# 9_RGB_TOUCH.net
KiCad netlist of a schematic drawn in Altium Designer
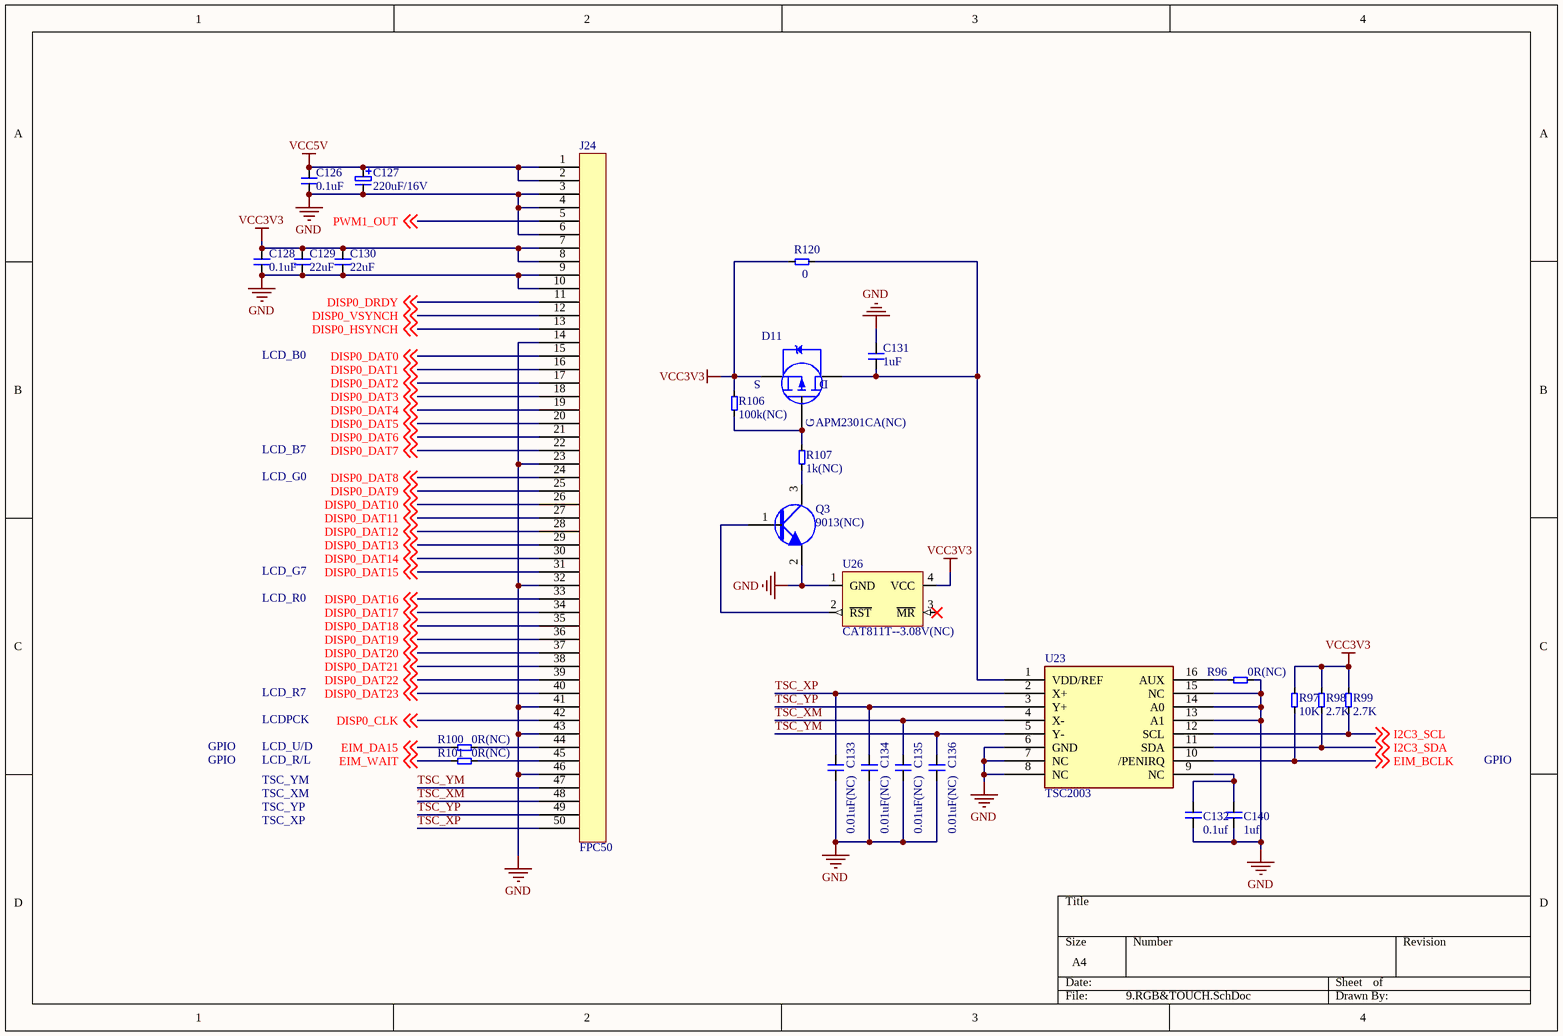
[diagram p0: 9.RGB&TOUCH.SchDoc]

(export (version "E")
  (design (tool "Eeschema 10.0.6"))
  (components
    (comp (ref "C126")
      (value "0.1uF")
      (footprint "0603C")
      (description "电容")
      (libsource (lib "LDT-SCH") (part "电容"))
    )
    (comp (ref "C127")
      (value "220uF/16V")
      (footprint "RAD-3/6")
      (description "直插电解电容")
      (libsource (lib "*") (part "直插电解电容"))
    )
    (comp (ref "C128")
      (value "0.1uF")
      (footprint "0603C")
      (description "电容")
      (libsource (lib "LDT-SCH") (part "电容"))
    )
    (comp (ref "C129")
      (value "22uF")
      (footprint "0805C")
      (description "电容")
      (libsource (lib "*") (part "电容"))
    )
    (comp (ref "C130")
      (value "22uF")
      (footprint "0805C")
      (description "电容")
      (libsource (lib "*") (part "电容"))
    )
    (comp (ref "C131")
      (value "1uF")
      (footprint "0603C")
      (description "电容")
      (libsource (lib "LDT-SCH") (part "电容"))
    )
    (comp (ref "C132")
      (value "0.1uf")
      (footprint "0603C")
      (description "电容")
      (libsource (lib "LDT1-SCH") (part "电容"))
    )
    (comp (ref "C133")
      (value "0.01uF(NC)")
      (footprint "0603C")
      (description "电容")
      (libsource (lib "LDT-SCH") (part "电容"))
    )
    (comp (ref "C134")
      (value "0.01uF(NC)")
      (footprint "0603C")
      (description "电容")
      (libsource (lib "LDT-SCH") (part "电容"))
    )
    (comp (ref "C135")
      (value "0.01uF(NC)")
      (footprint "0603C")
      (description "电容")
      (libsource (lib "LDT-SCH") (part "电容"))
    )
    (comp (ref "C136")
      (value "0.01uF(NC)")
      (footprint "0603C")
      (description "电容")
      (libsource (lib "LDT-SCH") (part "电容"))
    )
    (comp (ref "C140")
      (value "1uf")
      (footprint "0603C")
      (description "电容")
      (libsource (lib "LDT1-SCH") (part "电容"))
    )
    (comp (ref "D11")
      (value "APM2301CA(NC)")
      (footprint "SOT-23")
      (libsource (lib "LDT1-SCH") (part "APM2301CA"))
    )
    (comp (ref "J24")
      (value "FPC50")
      (footprint "FPC50-0.5-UP")
      (description "FPC CONNECTOR")
      (libsource (lib "LDT-SCH") (part "FPC50"))
    )
    (comp (ref "Q3") (value "9013(NC)") (footprint "SOT-23") (libsource (lib "LDT1-SCH") (part "9013")))
    (comp (ref "R96")
      (value "0R(NC)")
      (footprint "0603R")
      (description "电阻")
      (libsource (lib "LDT-SCH") (part "电阻"))
    )
    (comp (ref "R97")
      (value "10K")
      (footprint "0603R")
      (description "电阻")
      (libsource (lib "LDT-SCH") (part "电阻"))
    )
    (comp (ref "R98")
      (value "2.7K")
      (footprint "0603R")
      (description "电阻")
      (libsource (lib "LDT-SCH") (part "电阻"))
    )
    (comp (ref "R99")
      (value "2.7K")
      (footprint "0603R")
      (description "电阻")
      (libsource (lib "LDT-SCH") (part "电阻"))
    )
    (comp (ref "R100")
      (value "0R(NC)")
      (footprint "0603R")
      (description "电阻")
      (libsource (lib "LDT-SCH") (part "电阻"))
    )
    (comp (ref "R101")
      (value "0R(NC)")
      (footprint "0603R")
      (description "电阻")
      (libsource (lib "LDT-SCH") (part "电阻"))
    )
    (comp (ref "R106")
      (value "100k(NC)")
      (footprint "0603R")
      (description "电阻")
      (libsource (lib "LDT1-SCH") (part "电阻"))
    )
    (comp (ref "R107")
      (value "1k(NC)")
      (footprint "0603R")
      (description "电阻")
      (libsource (lib "LDT1-SCH") (part "电阻"))
    )
    (comp (ref "R120")
      (value "0")
      (footprint "0603R")
      (description "电阻")
      (libsource (lib "LDT1-SCH") (part "电阻"))
    )
    (comp (ref "U23")
      (value "TSC2003")
      (footprint "TSSOP16-PW")
      (description "TSC2007")
      (libsource (lib "LDT-SCH") (part "TSC2007IPW"))
    )
    (comp (ref "U26")
      (value "CAT811T--3.08V(NC)")
      (footprint "SOT143-4")
      (libsource (lib "MY") (part "CAT811T--3.08V"))
    )
  )
  (nets
    (net (code "1") (name "/TSC_XM") (class "Default")
      (node (ref "C135") (pin "1") (pintype "passive"))
      (node (ref "J24") (pin "48") (pinfunction "48_48") (pintype "passive"))
      (node (ref "U23") (pin "4") (pinfunction "X-_4") (pintype "passive"))
    )
    (net (code "2") (name "/TSC_XP") (class "Default")
      (node (ref "C133") (pin "1") (pintype "passive"))
      (node (ref "J24") (pin "50") (pinfunction "50_50") (pintype "passive"))
      (node (ref "U23") (pin "2") (pinfunction "X+_2") (pintype "passive"))
    )
    (net (code "3") (name "/TSC_YM") (class "Default")
      (node (ref "C136") (pin "1") (pintype "passive"))
      (node (ref "J24") (pin "47") (pinfunction "47_47") (pintype "passive"))
      (node (ref "U23") (pin "5") (pinfunction "Y-_5") (pintype "passive"))
    )
    (net (code "4") (name "/TSC_YP") (class "Default")
      (node (ref "C134") (pin "1") (pintype "passive"))
      (node (ref "J24") (pin "49") (pinfunction "49_49") (pintype "passive"))
      (node (ref "U23") (pin "3") (pinfunction "Y+_3") (pintype "passive"))
    )
    (net (code "5") (name "DISP0_CLK") (class "Default")
      (node (ref "J24") (pin "42") (pinfunction "42_42") (pintype "passive"))
    )
    (net (code "6") (name "DISP0_DAT0") (class "Default")
      (node (ref "J24") (pin "15") (pinfunction "15_15") (pintype "passive"))
    )
    (net (code "7") (name "DISP0_DAT1") (class "Default")
      (node (ref "J24") (pin "16") (pinfunction "16_16") (pintype "passive"))
    )
    (net (code "8") (name "DISP0_DAT2") (class "Default")
      (node (ref "J24") (pin "17") (pinfunction "17_17") (pintype "passive"))
    )
    (net (code "9") (name "DISP0_DAT3") (class "Default")
      (node (ref "J24") (pin "18") (pinfunction "18_18") (pintype "passive"))
    )
    (net (code "10") (name "DISP0_DAT4") (class "Default")
      (node (ref "J24") (pin "19") (pinfunction "19_19") (pintype "passive"))
    )
    (net (code "11") (name "DISP0_DAT5") (class "Default")
      (node (ref "J24") (pin "20") (pinfunction "20_20") (pintype "passive"))
    )
    (net (code "12") (name "DISP0_DAT6") (class "Default")
      (node (ref "J24") (pin "21") (pinfunction "21_21") (pintype "passive"))
    )
    (net (code "13") (name "DISP0_DAT7") (class "Default")
      (node (ref "J24") (pin "22") (pinfunction "22_22") (pintype "passive"))
    )
    (net (code "14") (name "DISP0_DAT8") (class "Default")
      (node (ref "J24") (pin "24") (pinfunction "24_24") (pintype "passive"))
    )
    (net (code "15") (name "DISP0_DAT9") (class "Default")
      (node (ref "J24") (pin "25") (pinfunction "25_25") (pintype "passive"))
    )
    (net (code "16") (name "DISP0_DAT10") (class "Default")
      (node (ref "J24") (pin "26") (pinfunction "26_26") (pintype "passive"))
    )
    (net (code "17") (name "DISP0_DAT11") (class "Default")
      (node (ref "J24") (pin "27") (pinfunction "27_27") (pintype "passive"))
    )
    (net (code "18") (name "DISP0_DAT12") (class "Default")
      (node (ref "J24") (pin "28") (pinfunction "28_28") (pintype "passive"))
    )
    (net (code "19") (name "DISP0_DAT13") (class "Default")
      (node (ref "J24") (pin "29") (pinfunction "29_29") (pintype "passive"))
    )
    (net (code "20") (name "DISP0_DAT14") (class "Default")
      (node (ref "J24") (pin "30") (pinfunction "30_30") (pintype "passive"))
    )
    (net (code "21") (name "DISP0_DAT15") (class "Default")
      (node (ref "J24") (pin "31") (pinfunction "31_31") (pintype "passive"))
    )
    (net (code "22") (name "DISP0_DAT16") (class "Default")
      (node (ref "J24") (pin "33") (pinfunction "33_33") (pintype "passive"))
    )
    (net (code "23") (name "DISP0_DAT17") (class "Default")
      (node (ref "J24") (pin "34") (pinfunction "34_34") (pintype "passive"))
    )
    (net (code "24") (name "DISP0_DAT18") (class "Default")
      (node (ref "J24") (pin "35") (pinfunction "35_35") (pintype "passive"))
    )
    (net (code "25") (name "DISP0_DAT19") (class "Default")
      (node (ref "J24") (pin "36") (pinfunction "36_36") (pintype "passive"))
    )
    (net (code "26") (name "DISP0_DAT20") (class "Default")
      (node (ref "J24") (pin "37") (pinfunction "37_37") (pintype "passive"))
    )
    (net (code "27") (name "DISP0_DAT21") (class "Default")
      (node (ref "J24") (pin "38") (pinfunction "38_38") (pintype "passive"))
    )
    (net (code "28") (name "DISP0_DAT22") (class "Default")
      (node (ref "J24") (pin "39") (pinfunction "39_39") (pintype "passive"))
    )
    (net (code "29") (name "DISP0_DAT23") (class "Default")
      (node (ref "J24") (pin "40") (pinfunction "40_40") (pintype "passive"))
    )
    (net (code "30") (name "DISP0_DRDY") (class "Default")
      (node (ref "J24") (pin "11") (pinfunction "11_11") (pintype "passive"))
    )
    (net (code "31") (name "DISP0_HSYNCH") (class "Default")
      (node (ref "J24") (pin "13") (pinfunction "13_13") (pintype "passive"))
    )
    (net (code "32") (name "DISP0_VSYNCH") (class "Default")
      (node (ref "J24") (pin "12") (pinfunction "12_12") (pintype "passive"))
    )
    (net (code "33") (name "EIM_BCLK") (class "Default")
      (node (ref "R97") (pin "2") (pintype "passive"))
      (node (ref "U23") (pin "10") (pinfunction "/PENIRQ_10") (pintype "passive"))
    )
    (net (code "34") (name "EIM_DA15") (class "Default") (node (ref "R100") (pin "2") (pintype "passive")))
    (net (code "35") (name "EIM_WAIT") (class "Default") (node (ref "R101") (pin "2") (pintype "passive")))
    (net (code "36") (name "GND") (class "Default")
      (node (ref "C126") (pin "2") (pintype "passive"))
      (node (ref "C127") (pin "2") (pintype "passive"))
      (node (ref "C128") (pin "2") (pintype "passive"))
      (node (ref "C129") (pin "1") (pintype "passive"))
      (node (ref "C130") (pin "1") (pintype "passive"))
      (node (ref "C131") (pin "1") (pintype "passive"))
      (node (ref "C132") (pin "2") (pintype "passive"))
      (node (ref "C133") (pin "2") (pintype "passive"))
      (node (ref "C134") (pin "2") (pintype "passive"))
      (node (ref "C135") (pin "2") (pintype "passive"))
      (node (ref "C136") (pin "2") (pintype "passive"))
      (node (ref "C140") (pin "2") (pintype "passive"))
      (node (ref "J24") (pin "10") (pinfunction "10_10") (pintype "passive"))
      (node (ref "J24") (pin "14") (pinfunction "14_14") (pintype "passive"))
      (node (ref "J24") (pin "23") (pinfunction "23_23") (pintype "passive"))
      (node (ref "J24") (pin "3") (pinfunction "3_3") (pintype "passive"))
      (node (ref "J24") (pin "32") (pinfunction "32_32") (pintype "passive"))
      (node (ref "J24") (pin "4") (pinfunction "4_4") (pintype "passive"))
      (node (ref "J24") (pin "41") (pinfunction "41_41") (pintype "passive"))
      (node (ref "J24") (pin "43") (pinfunction "43_43") (pintype "passive"))
      (node (ref "J24") (pin "46") (pinfunction "46_46") (pintype "passive"))
      (node (ref "J24") (pin "6") (pinfunction "6_6") (pintype "passive"))
      (node (ref "J24") (pin "9") (pinfunction "9_9") (pintype "passive"))
      (node (ref "Q3") (pin "2") (pintype "passive"))
      (node (ref "R96") (pin "1") (pintype "passive"))
      (node (ref "U23") (pin "13") (pinfunction "A1_13") (pintype "passive"))
      (node (ref "U23") (pin "14") (pinfunction "A0_14") (pintype "passive"))
      (node (ref "U23") (pin "15") (pinfunction "NC_15") (pintype "passive"))
      (node (ref "U23") (pin "6") (pinfunction "GND_6") (pintype "passive"))
      (node (ref "U23") (pin "7") (pinfunction "NC_7") (pintype "passive"))
      (node (ref "U23") (pin "8") (pinfunction "NC_8") (pintype "passive"))
      (node (ref "U26") (pin "1") (pinfunction "GND_1") (pintype "power_in"))
    )
    (net (code "37") (name "I2C3_SCL") (class "Default")
      (node (ref "R99") (pin "2") (pintype "passive"))
      (node (ref "U23") (pin "12") (pinfunction "SCL_12") (pintype "passive"))
    )
    (net (code "38") (name "I2C3_SDA") (class "Default")
      (node (ref "R98") (pin "2") (pintype "passive"))
      (node (ref "U23") (pin "11") (pinfunction "SDA_11") (pintype "passive"))
    )
    (net (code "39") (name "Net-(C132-Pad1)") (class "Default")
      (node (ref "C132") (pin "1") (pintype "passive"))
      (node (ref "C140") (pin "1") (pintype "passive"))
      (node (ref "U23") (pin "9") (pinfunction "NC_9") (pintype "passive"))
    )
    (net (code "40") (name "Net-(D11-Pad1)") (class "Default")
      (node (ref "D11") (pin "1") (pintype "passive"))
      (node (ref "R106") (pin "1") (pintype "passive"))
      (node (ref "R107") (pin "2") (pintype "passive"))
    )
    (net (code "41") (name "Net-(J24-Pad44)") (class "Default")
      (node (ref "J24") (pin "44") (pinfunction "44_44") (pintype "passive"))
      (node (ref "R100") (pin "1") (pintype "passive"))
    )
    (net (code "42") (name "Net-(J24-Pad45)") (class "Default")
      (node (ref "J24") (pin "45") (pinfunction "45_45") (pintype "passive"))
      (node (ref "R101") (pin "1") (pintype "passive"))
    )
    (net (code "43") (name "Net-(Q3-Pad3)") (class "Default")
      (node (ref "Q3") (pin "3") (pintype "passive"))
      (node (ref "R107") (pin "1") (pintype "passive"))
    )
    (net (code "44") (name "Net-(U23-AUX)") (class "Default")
      (node (ref "R96") (pin "2") (pintype "passive"))
      (node (ref "U23") (pin "16") (pinfunction "AUX_16") (pintype "passive"))
    )
    (net (code "45") (name "Net-(U23-VDD{slash}REF)") (class "Default")
      (node (ref "C131") (pin "2") (pintype "passive"))
      (node (ref "D11") (pin "3") (pintype "passive"))
      (node (ref "R120") (pin "2") (pintype "passive"))
      (node (ref "U23") (pin "1") (pinfunction "VDD/REF_1") (pintype "passive"))
    )
    (net (code "46") (name "Net-(U26-~{RST})") (class "Default")
      (node (ref "Q3") (pin "1") (pintype "passive"))
      (node (ref "U26") (pin "2") (pinfunction "~{RST}_2") (pintype "output"))
    )
    (net (code "47") (name "PWM1_OUT") (class "Default")
      (node (ref "J24") (pin "5") (pinfunction "5_5") (pintype "passive"))
    )
    (net (code "48") (name "VCC3V3") (class "Default")
      (node (ref "C128") (pin "1") (pintype "passive"))
      (node (ref "C129") (pin "2") (pintype "passive"))
      (node (ref "C130") (pin "2") (pintype "passive"))
      (node (ref "D11") (pin "2") (pintype "passive"))
      (node (ref "J24") (pin "7") (pinfunction "7_7") (pintype "passive"))
      (node (ref "J24") (pin "8") (pinfunction "8_8") (pintype "passive"))
      (node (ref "R106") (pin "2") (pintype "passive"))
      (node (ref "R120") (pin "1") (pintype "passive"))
      (node (ref "R97") (pin "1") (pintype "passive"))
      (node (ref "R98") (pin "1") (pintype "passive"))
      (node (ref "R99") (pin "1") (pintype "passive"))
      (node (ref "U26") (pin "4") (pinfunction "VCC_4") (pintype "power_in"))
    )
    (net (code "49") (name "VCC5V") (class "Default")
      (node (ref "C126") (pin "1") (pintype "passive"))
      (node (ref "C127") (pin "1") (pintype "passive"))
      (node (ref "J24") (pin "1") (pinfunction "1_1") (pintype "passive"))
      (node (ref "J24") (pin "2") (pinfunction "2_2") (pintype "passive"))
    )
    (net (code "50") (name "unconnected-(U26-~{MR}-Pad3)") (class "Default")
      (node (ref "U26") (pin "3") (pinfunction "~{MR}_3") (pintype "input+no_connect"))
    )
  )
)
